# extBoard.net
KiCad netlist of a schematic drawn in EAGLE
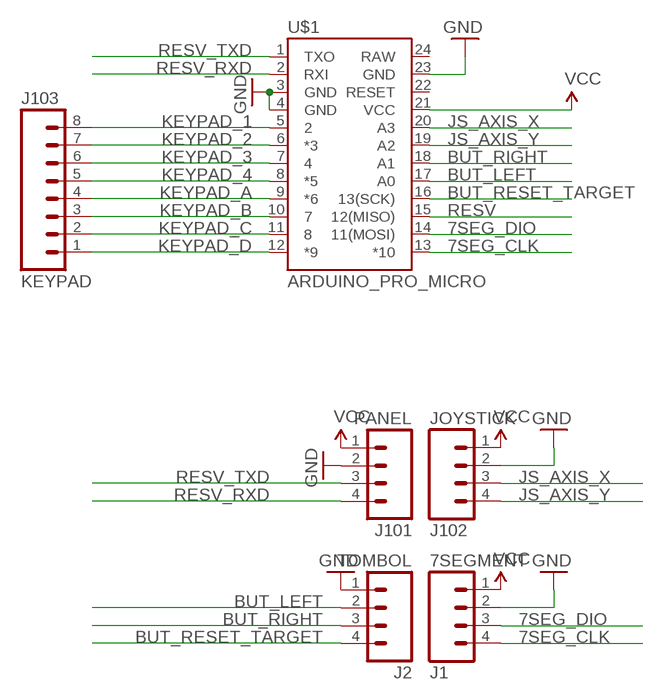
[diagram p0: schematic, sheet 1]

(export (version "E")
  (design (tool "Eeschema 10.0.6"))
  (components
    (comp (ref "J1")
      (value "7SEGMENT")
      (footprint "eagle-import:XH-4-RA")
      (libsource (lib "eagle-import") (part "M04-XH-RA"))
    )
    (comp (ref "J2")
      (value "TOMBOL")
      (footprint "eagle-import:XH-4-RA")
      (libsource (lib "eagle-import") (part "M04-XH-RA"))
    )
    (comp (ref "J101")
      (value "PANEL")
      (footprint "eagle-import:XH-4-RA")
      (libsource (lib "eagle-import") (part "M04-XH-RA"))
    )
    (comp (ref "J102")
      (value "JOYSTICK")
      (footprint "eagle-import:XH-4-RA")
      (libsource (lib "eagle-import") (part "M04-XH-RA"))
    )
    (comp (ref "J103")
      (value "KEYPAD")
      (footprint "eagle-import:XH-8-RA")
      (libsource (lib "eagle-import") (part "M08-XH-RA"))
    )
    (comp (ref "U$1")
      (value "ARDUINO_PRO_MICRO")
      (footprint "eagle-import:ARDUINO_PRO_MICRO")
      (libsource (lib "eagle-import") (part "ARDUINO_PRO_MICRO"))
    )
  )
  (nets
    (net (code "1") (name "/7SEG_CLK") (class "Default")
      (node (ref "J1") (pin "4") (pinfunction "4_4") (pintype "passive"))
      (node (ref "U$1") (pin "13") (pinfunction "*10_13") (pintype "bidirectional"))
    )
    (net (code "2") (name "/7SEG_DIO") (class "Default")
      (node (ref "J1") (pin "3") (pinfunction "3_3") (pintype "passive"))
      (node (ref "U$1") (pin "14") (pinfunction "11(MOSI)_14") (pintype "bidirectional"))
    )
    (net (code "3") (name "/BUT_LEFT") (class "Default")
      (node (ref "J2") (pin "2") (pinfunction "2_2") (pintype "passive"))
      (node (ref "U$1") (pin "17") (pinfunction "A0_17") (pintype "bidirectional"))
    )
    (net (code "4") (name "/BUT_RESET_TARGET") (class "Default")
      (node (ref "J2") (pin "4") (pinfunction "4_4") (pintype "passive"))
      (node (ref "U$1") (pin "16") (pinfunction "13(SCK)_16") (pintype "bidirectional"))
    )
    (net (code "5") (name "/BUT_RIGHT") (class "Default")
      (node (ref "J2") (pin "3") (pinfunction "3_3") (pintype "passive"))
      (node (ref "U$1") (pin "18") (pinfunction "A1_18") (pintype "bidirectional"))
    )
    (net (code "6") (name "/JS_AXIS_X") (class "Default")
      (node (ref "J102") (pin "3") (pinfunction "3_3") (pintype "passive"))
      (node (ref "U$1") (pin "20") (pinfunction "A3_20") (pintype "bidirectional"))
    )
    (net (code "7") (name "/JS_AXIS_Y") (class "Default")
      (node (ref "J102") (pin "4") (pinfunction "4_4") (pintype "passive"))
      (node (ref "U$1") (pin "19") (pinfunction "A2_19") (pintype "bidirectional"))
    )
    (net (code "8") (name "/KEYPAD_1") (class "Default")
      (node (ref "J103") (pin "8") (pinfunction "8_8") (pintype "passive"))
      (node (ref "U$1") (pin "5") (pinfunction "2_5") (pintype "bidirectional"))
    )
    (net (code "9") (name "/KEYPAD_2") (class "Default")
      (node (ref "J103") (pin "7") (pinfunction "7_7") (pintype "passive"))
      (node (ref "U$1") (pin "6") (pinfunction "*3_6") (pintype "bidirectional"))
    )
    (net (code "10") (name "/KEYPAD_3") (class "Default")
      (node (ref "J103") (pin "6") (pinfunction "6_6") (pintype "passive"))
      (node (ref "U$1") (pin "7") (pinfunction "4_7") (pintype "bidirectional"))
    )
    (net (code "11") (name "/KEYPAD_4") (class "Default")
      (node (ref "J103") (pin "5") (pinfunction "5_5") (pintype "passive"))
      (node (ref "U$1") (pin "8") (pinfunction "*5_8") (pintype "bidirectional"))
    )
    (net (code "12") (name "/KEYPAD_A") (class "Default")
      (node (ref "J103") (pin "4") (pinfunction "4_4") (pintype "passive"))
      (node (ref "U$1") (pin "9") (pinfunction "*6_9") (pintype "bidirectional"))
    )
    (net (code "13") (name "/KEYPAD_B") (class "Default")
      (node (ref "J103") (pin "3") (pinfunction "3_3") (pintype "passive"))
      (node (ref "U$1") (pin "10") (pinfunction "7_10") (pintype "bidirectional"))
    )
    (net (code "14") (name "/KEYPAD_C") (class "Default")
      (node (ref "J103") (pin "2") (pinfunction "2_2") (pintype "passive"))
      (node (ref "U$1") (pin "11") (pinfunction "8_11") (pintype "bidirectional"))
    )
    (net (code "15") (name "/KEYPAD_D") (class "Default")
      (node (ref "J103") (pin "1") (pinfunction "1_1") (pintype "passive"))
      (node (ref "U$1") (pin "12") (pinfunction "*9_12") (pintype "bidirectional"))
    )
    (net (code "16") (name "/RESV") (class "Default")
      (node (ref "U$1") (pin "15") (pinfunction "12(MISO)_15") (pintype "bidirectional"))
    )
    (net (code "17") (name "/RESV_RXD") (class "Default")
      (node (ref "J101") (pin "4") (pinfunction "4_4") (pintype "passive"))
      (node (ref "U$1") (pin "2") (pinfunction "RXI_2") (pintype "bidirectional"))
    )
    (net (code "18") (name "/RESV_TXD") (class "Default")
      (node (ref "J101") (pin "3") (pinfunction "3_3") (pintype "passive"))
      (node (ref "U$1") (pin "1") (pinfunction "TXO_1") (pintype "bidirectional"))
    )
    (net (code "19") (name "GND") (class "Default")
      (node (ref "J1") (pin "2") (pinfunction "2_2") (pintype "passive"))
      (node (ref "J101") (pin "2") (pinfunction "2_2") (pintype "passive"))
      (node (ref "J102") (pin "2") (pinfunction "2_2") (pintype "passive"))
      (node (ref "J2") (pin "1") (pinfunction "1_1") (pintype "passive"))
      (node (ref "U$1") (pin "23") (pinfunction "GND_23") (pintype "bidirectional"))
      (node (ref "U$1") (pin "3") (pinfunction "GND_3") (pintype "bidirectional"))
      (node (ref "U$1") (pin "4") (pinfunction "GND_4") (pintype "bidirectional"))
    )
    (net (code "20") (name "VCC") (class "Default")
      (node (ref "J1") (pin "1") (pinfunction "1_1") (pintype "passive"))
      (node (ref "J101") (pin "1") (pinfunction "1_1") (pintype "passive"))
      (node (ref "J102") (pin "1") (pinfunction "1_1") (pintype "passive"))
      (node (ref "U$1") (pin "21") (pinfunction "VCC_21") (pintype "bidirectional"))
    )
    (net (code "21") (name "unconnected-(U$1-RAW-Pad24)") (class "Default")
      (node (ref "U$1") (pin "24") (pinfunction "RAW_24") (pintype "bidirectional"))
    )
    (net (code "22") (name "unconnected-(U$1-RESET-Pad22)") (class "Default")
      (node (ref "U$1") (pin "22") (pinfunction "RESET_22") (pintype "bidirectional"))
    )
  )
)
